# MAKKI_ISMAIL_ESPS3_CAM.net
KiCad netlist of a schematic drawn in EAGLE
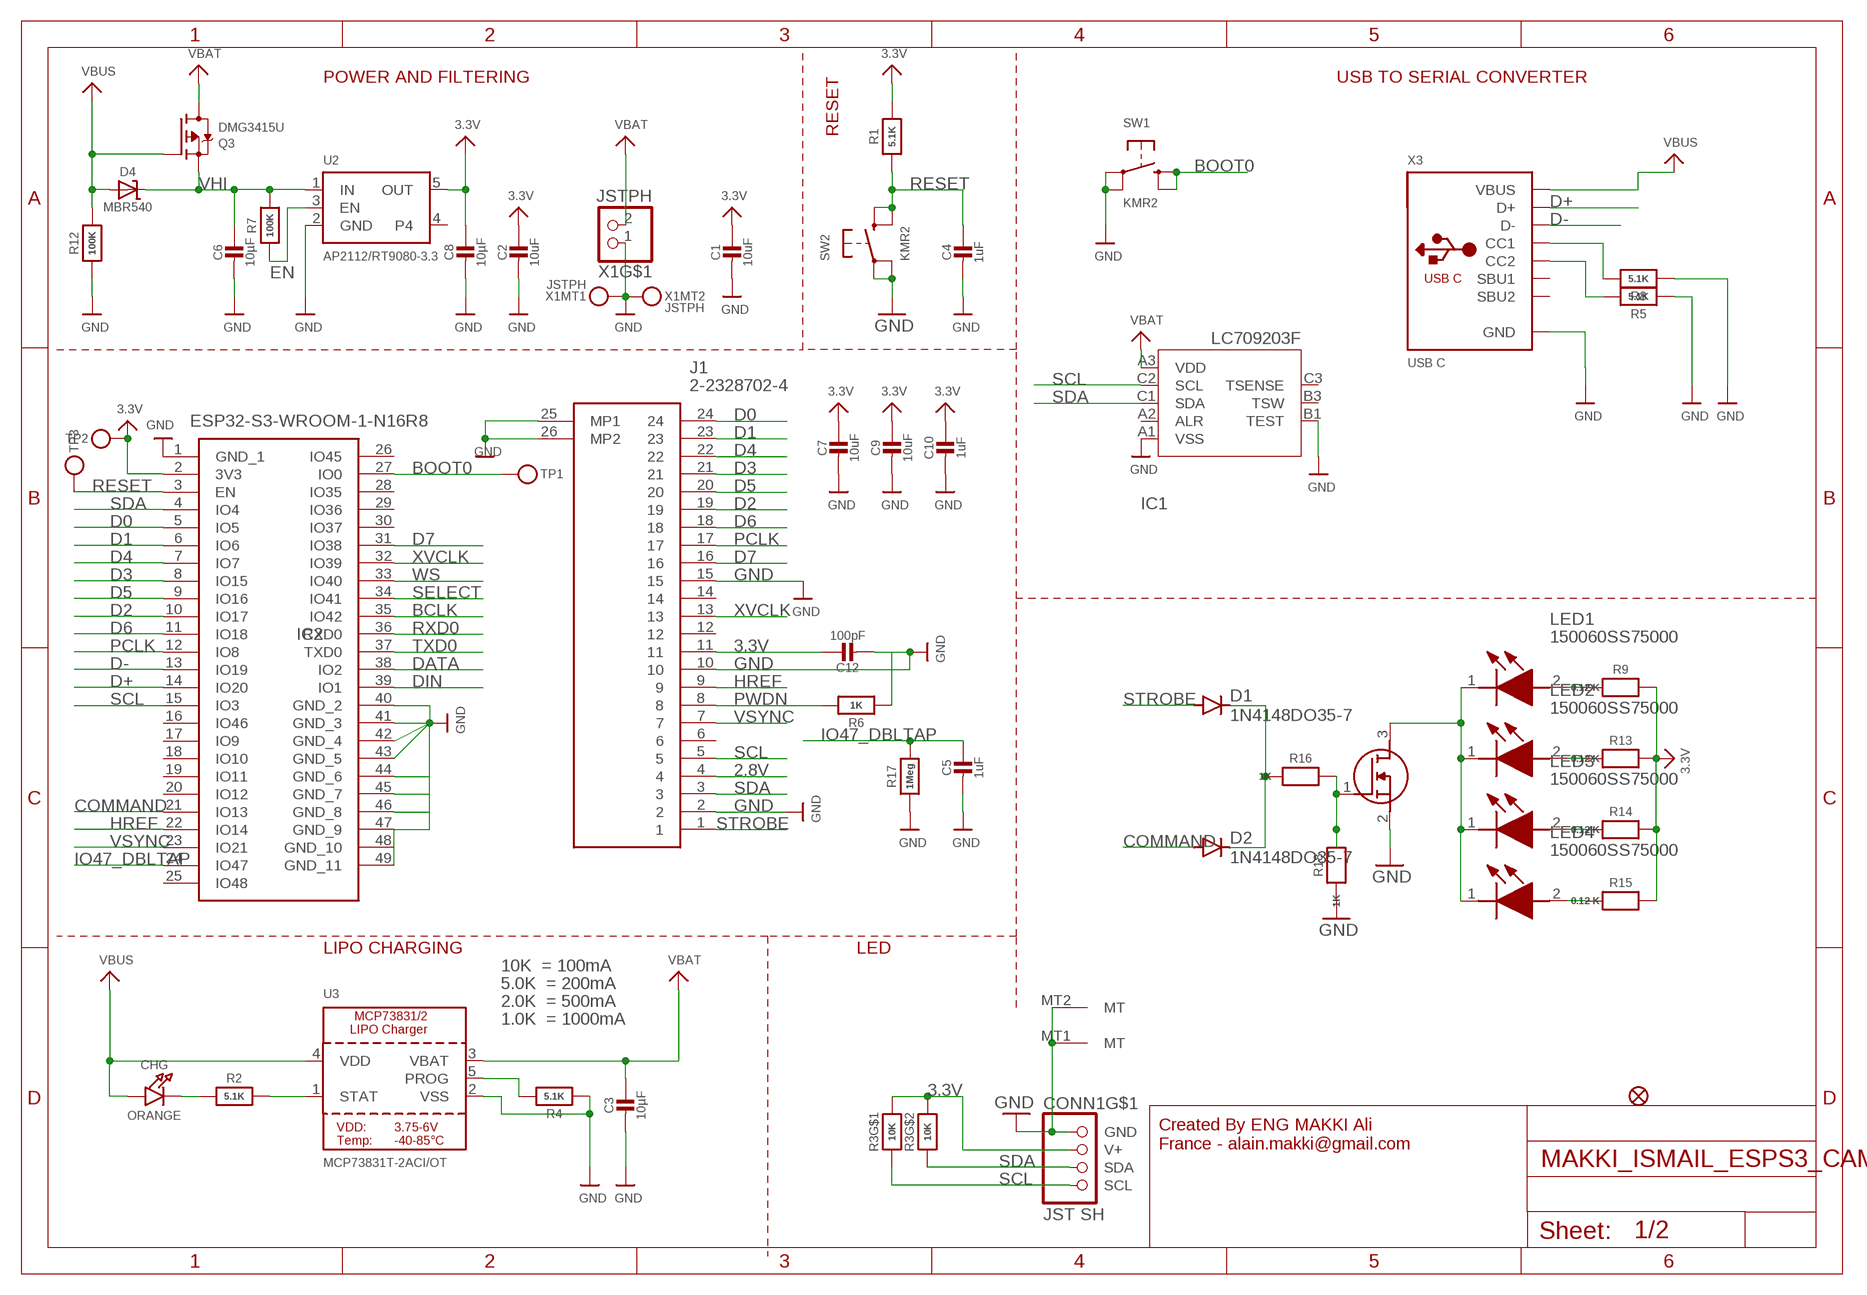
[diagram p0: schematic, sheet 1]
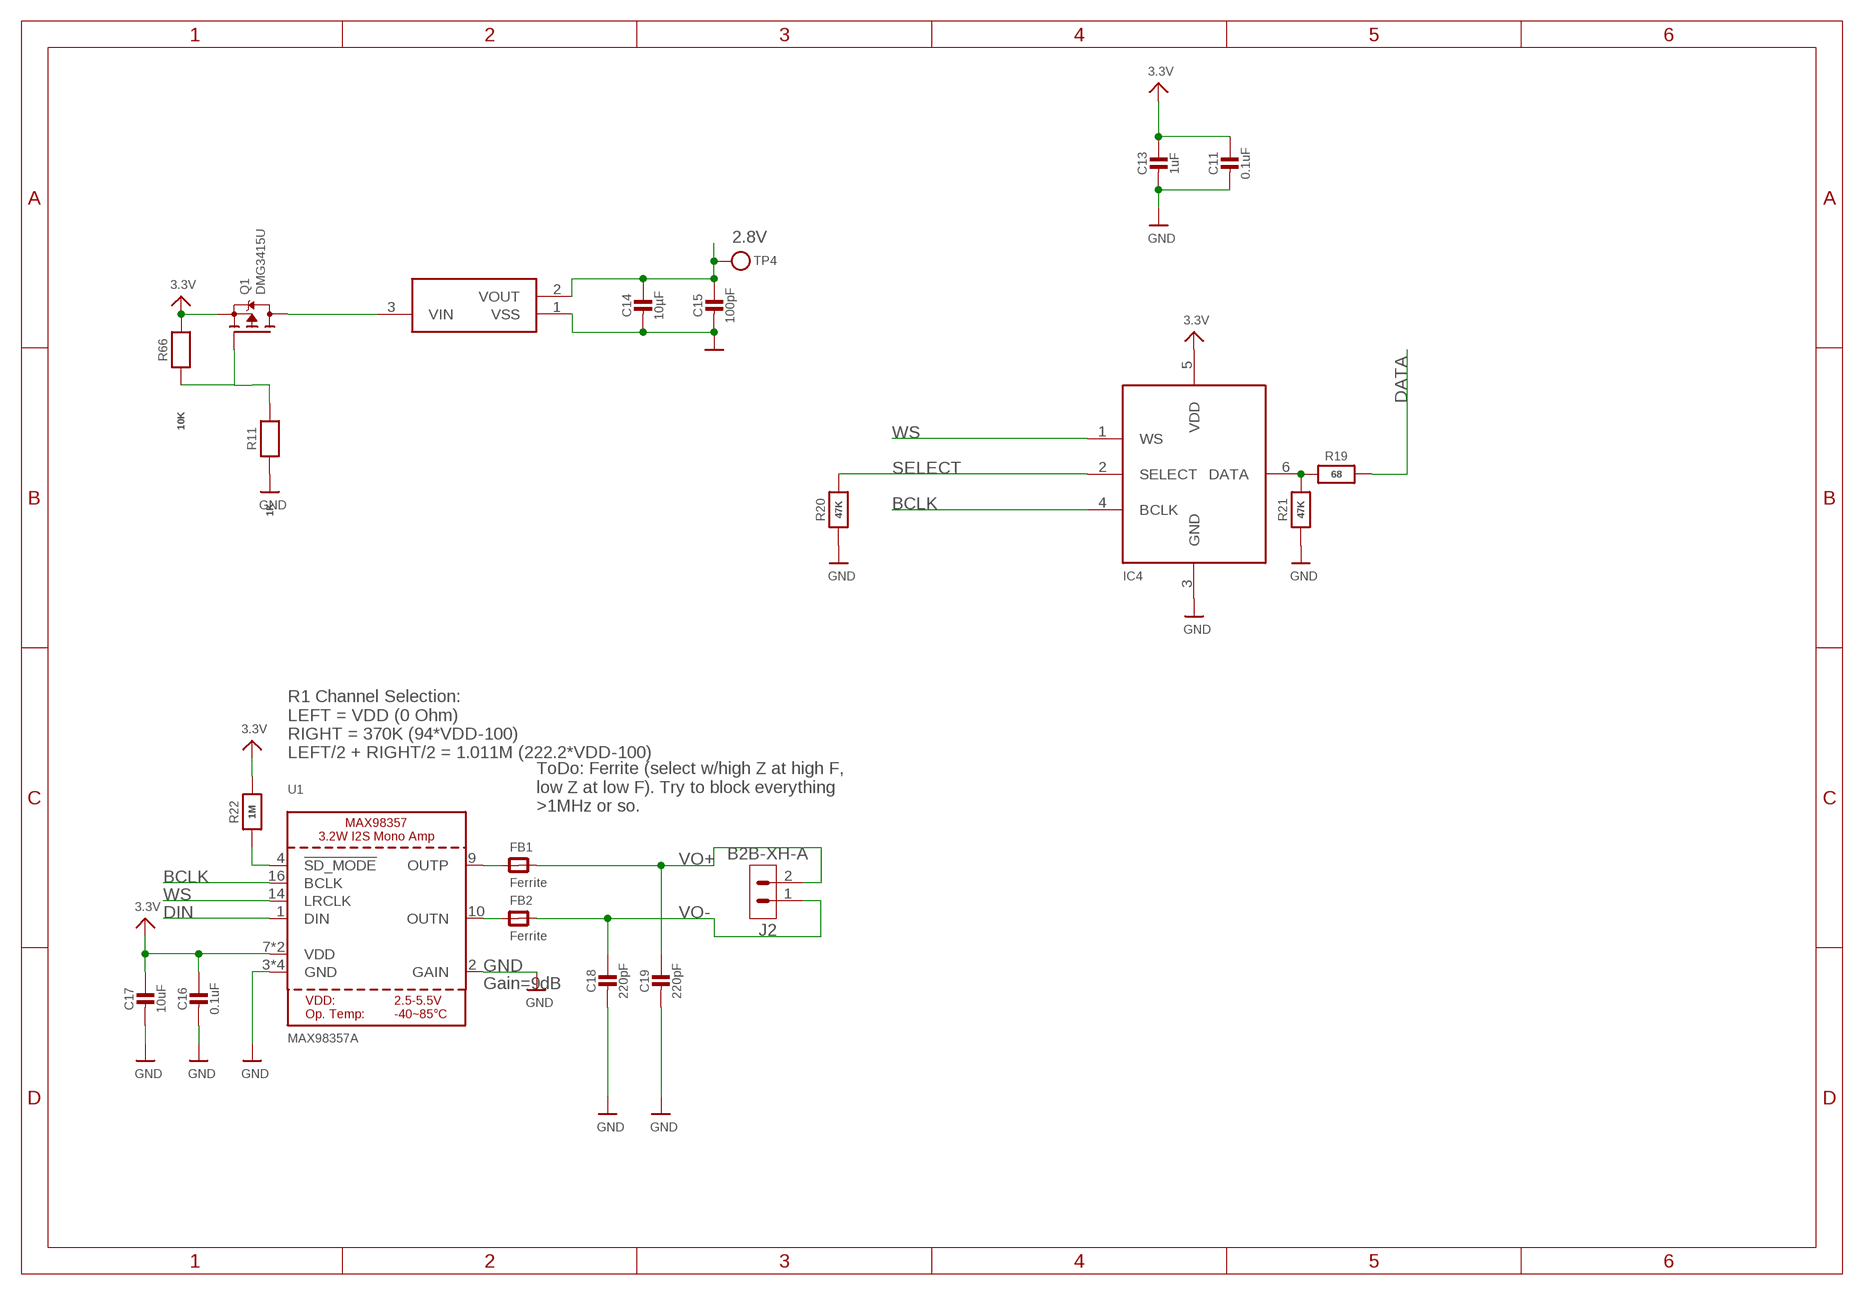
[diagram p1: schematic, sheet 2]

(export (version "E")
  (design (tool "Eeschema 10.0.6"))
  (components
    (comp (ref "C1")
      (value "10uF")
      (footprint "eagle-import:0805-NO")
      (libsource (lib "eagle-import") (part "CAP_CERAMIC0805-NOOUTLINE"))
    )
    (comp (ref "C2")
      (value "10uF")
      (footprint "eagle-import:0805-NO")
      (libsource (lib "eagle-import") (part "CAP_CERAMIC0805-NOOUTLINE"))
    )
    (comp (ref "C3")
      (value "10µF")
      (footprint "eagle-import:0805-NO")
      (libsource (lib "eagle-import") (part "CAP_CERAMIC0805-NOOUTLINE"))
    )
    (comp (ref "C4")
      (value "1uF")
      (footprint "eagle-import:0603-NO")
      (libsource (lib "eagle-import") (part "CAP_CERAMIC0603_NO"))
    )
    (comp (ref "C5")
      (value "1uF")
      (footprint "eagle-import:0603-NO")
      (libsource (lib "eagle-import") (part "CAP_CERAMIC0603_NO"))
    )
    (comp (ref "C6")
      (value "10µF")
      (footprint "eagle-import:0805-NO")
      (libsource (lib "eagle-import") (part "CAP_CERAMIC0805-NOOUTLINE"))
    )
    (comp (ref "C7")
      (value "10uF")
      (footprint "eagle-import:0805-NO")
      (libsource (lib "eagle-import") (part "CAP_CERAMIC0805-NOOUTLINE"))
    )
    (comp (ref "C8")
      (value "10µF")
      (footprint "eagle-import:0805-NO")
      (fields (field (name "REV") "C"))
      (libsource (lib "eagle-import") (part "CAP_CERAMIC0805-NOOUTLINE"))
    )
    (comp (ref "C9")
      (value "10uF")
      (footprint "eagle-import:0805-NO")
      (libsource (lib "eagle-import") (part "CAP_CERAMIC0805-NOOUTLINE"))
    )
    (comp (ref "C10")
      (value "1uF")
      (footprint "eagle-import:0603-NO")
      (libsource (lib "eagle-import") (part "CAP_CERAMIC0603_NO"))
    )
    (comp (ref "C12")
      (value "100pF")
      (footprint "eagle-import:0805-NO")
      (libsource (lib "eagle-import") (part "CAP_CERAMIC0805-NOOUTLINE"))
    )
    (comp (ref "CHG")
      (value "ORANGE")
      (footprint "eagle-import:CHIPLED_0603_NOOUTLINE")
      (libsource (lib "eagle-import") (part "LED0603_NOOUTLINE"))
    )
    (comp (ref "CONN1")
      (value "JST SH")
      (footprint "eagle-import:JST_SH4_RA")
      (libsource (lib "eagle-import") (part "STEMMA_I2C_QTRA"))
    )
    (comp (ref "D1")
      (value "1N4148DO35-7")
      (footprint "eagle-import:DO35-7")
      (libsource (lib "eagle-import") (part "1N4148DO35-7"))
    )
    (comp (ref "D2")
      (value "1N4148DO35-7")
      (footprint "eagle-import:DO35-7")
      (libsource (lib "eagle-import") (part "1N4148DO35-7"))
    )
    (comp (ref "D4")
      (value "MBR540")
      (footprint "eagle-import:SOD-123")
      (libsource (lib "eagle-import") (part "DIODE-SCHOTTKYSOD-123"))
    )
    (comp (ref "IC1")
      (value "LC709203F/MH")
      (footprint "eagle-import:WLCSP9")
      (libsource (lib "eagle-import") (part "LC709203F/MH"))
    )
    (comp (ref "IC2")
      (value "ESP32-S3-WROOM-1-N16R8")
      (footprint "eagle-import:ESP32S3WROOM1N16R8")
      (fields (field (name "MOUSER_PART_NUMBER") "356-ESP32S3WRM1N16R8"))
      (libsource (lib "eagle-import") (part "ESP32-S3-WROOM-1-N16R8"))
    )
    (comp (ref "J1")
      (value "2-2328702-4")
      (footprint "eagle-import:223287024")
      (fields (field (name "MOUSER_PART_NUMBER") "571-2-2328702-4"))
      (libsource (lib "eagle-import") (part "2-2328702-4"))
    )
    (comp (ref "LED1")
      (value "150060SS75000")
      (footprint "eagle-import:LEDC1608X80N")
      (fields (field (name "MOUSER_PART_NUMBER") "710-150060SS75000"))
      (libsource (lib "eagle-import") (part "150060SS75000"))
    )
    (comp (ref "LED2")
      (value "150060SS75000")
      (footprint "eagle-import:LEDC1608X80N")
      (fields (field (name "MOUSER_PART_NUMBER") "710-150060SS75000"))
      (libsource (lib "eagle-import") (part "150060SS75000"))
    )
    (comp (ref "LED3")
      (value "150060SS75000")
      (footprint "eagle-import:LEDC1608X80N")
      (fields (field (name "MOUSER_PART_NUMBER") "710-150060SS75000"))
      (libsource (lib "eagle-import") (part "150060SS75000"))
    )
    (comp (ref "LED4")
      (value "150060SS75000")
      (footprint "eagle-import:LEDC1608X80N")
      (fields (field (name "MOUSER_PART_NUMBER") "710-150060SS75000"))
      (libsource (lib "eagle-import") (part "150060SS75000"))
    )
    (comp (ref "Q2")
      (value "2N7002")
      (footprint "eagle-import:SOT96P240X120-3N")
      (fields (field (name "MOUSER_PART_NUMBER") "512-2N7002"))
      (libsource (lib "eagle-import") (part "2N7002"))
    )
    (comp (ref "Q3")
      (value "DMG3415U")
      (footprint "eagle-import:SOT23-R")
      (libsource (lib "eagle-import") (part "MOSFET-P"))
    )
    (comp (ref "R1")
      (value "5.1K")
      (footprint "eagle-import:0603-NO")
      (libsource (lib "eagle-import") (part "RESISTOR_0603_NOOUT"))
    )
    (comp (ref "R2")
      (value "5.1K")
      (footprint "eagle-import:0603-NO")
      (libsource (lib "eagle-import") (part "RESISTOR_0603_NOOUT"))
    )
    (comp (ref "R3")
      (value "10K")
      (footprint "eagle-import:RESPACK_4X0603")
      (libsource (lib "eagle-import") (part "RESISTOR_4PACK"))
    )
    (comp (ref "R4")
      (value "5.1K")
      (footprint "eagle-import:0603-NO")
      (libsource (lib "eagle-import") (part "RESISTOR_0603_NOOUT"))
    )
    (comp (ref "R5")
      (value "5.1K")
      (footprint "eagle-import:0603-NO")
      (libsource (lib "eagle-import") (part "RESISTOR_0603_NOOUT"))
    )
    (comp (ref "R6")
      (value "1K")
      (footprint "eagle-import:0603-NO")
      (libsource (lib "eagle-import") (part "RESISTOR_0603_NOOUT"))
    )
    (comp (ref "R7")
      (value "100K")
      (footprint "eagle-import:0603-NO")
      (libsource (lib "eagle-import") (part "RESISTOR_0603_NOOUT"))
    )
    (comp (ref "R8")
      (value "5.1K")
      (footprint "eagle-import:0603-NO")
      (libsource (lib "eagle-import") (part "RESISTOR_0603_NOOUT"))
    )
    (comp (ref "R9")
      (value "0.12 K")
      (footprint "eagle-import:0603-NO")
      (libsource (lib "eagle-import") (part "RESISTOR_0603_NOOUT"))
    )
    (comp (ref "R12")
      (value "100K")
      (footprint "eagle-import:0603-NO")
      (libsource (lib "eagle-import") (part "RESISTOR_0603_NOOUT"))
    )
    (comp (ref "R13")
      (value "0.12 K")
      (footprint "eagle-import:0603-NO")
      (libsource (lib "eagle-import") (part "RESISTOR_0603_NOOUT"))
    )
    (comp (ref "R14")
      (value "0.12 K")
      (footprint "eagle-import:0603-NO")
      (libsource (lib "eagle-import") (part "RESISTOR_0603_NOOUT"))
    )
    (comp (ref "R15")
      (value "0.12 K")
      (footprint "eagle-import:0603-NO")
      (libsource (lib "eagle-import") (part "RESISTOR_0603_NOOUT"))
    )
    (comp (ref "R16")
      (value "1K")
      (footprint "eagle-import:0603-NO")
      (libsource (lib "eagle-import") (part "RESISTOR_0603_NOOUT"))
    )
    (comp (ref "R17")
      (value "1Meg")
      (footprint "eagle-import:0603-NO")
      (libsource (lib "eagle-import") (part "RESISTOR_0603_NOOUT"))
    )
    (comp (ref "R18")
      (value "1K")
      (footprint "eagle-import:0603-NO")
      (libsource (lib "eagle-import") (part "RESISTOR_0603_NOOUT"))
    )
    (comp (ref "SW1")
      (value "KMR2")
      (footprint "eagle-import:BTN_KMR2_4.6X2.8")
      (libsource (lib "eagle-import") (part "SWITCH_TACT_SMT4.6X2.8"))
    )
    (comp (ref "SW2")
      (value "KMR2")
      (footprint "eagle-import:BTN_KMR2_4.6X2.8")
      (libsource (lib "eagle-import") (part "SWITCH_TACT_SMT4.6X2.8"))
    )
    (comp (ref "TP1")
      (value "TESTPOINTROUND1.5MMNO")
      (footprint "eagle-import:TESTPOINT_ROUND_1.5MM_NO")
      (libsource (lib "eagle-import") (part "TESTPOINTROUND1.5MMNO"))
    )
    (comp (ref "TP2")
      (value "TESTPOINTROUND1.5MMNO")
      (footprint "eagle-import:TESTPOINT_ROUND_1.5MM_NO")
      (libsource (lib "eagle-import") (part "TESTPOINTROUND1.5MMNO"))
    )
    (comp (ref "TP3")
      (value "TESTPOINTROUND1.5MMNO")
      (footprint "eagle-import:TESTPOINT_ROUND_1.5MM_NO")
      (libsource (lib "eagle-import") (part "TESTPOINTROUND1.5MMNO"))
    )
    (comp (ref "U$34")
      (value "FIDUCIAL_1MM")
      (footprint "eagle-import:FIDUCIAL_1MM")
      (libsource (lib "eagle-import") (part "FIDUCIAL_1MM"))
    )
    (comp (ref "U2")
      (value "AP2112/RT9080-3.3")
      (footprint "eagle-import:SOT23-5")
      (libsource (lib "eagle-import") (part "VREG_SOT23-5"))
    )
    (comp (ref "U3")
      (value "MCP73831T-2ACI/OT")
      (footprint "eagle-import:SOT23-5")
      (libsource (lib "eagle-import") (part "MCP73831/2"))
    )
    (comp (ref "X1")
      (value "JSTPH")
      (footprint "eagle-import:JSTPH2_BATT")
      (libsource (lib "eagle-import") (part "CON_JST_PH_2PIN_MT_BATT"))
    )
    (comp (ref "X3")
      (value "USB C")
      (footprint "eagle-import:USB_C_CUSB31-CFM2AX-01-X")
      (libsource (lib "eagle-import") (part "USB_C"))
    )
    (comp (ref "C11")
      (value "0.1uF")
      (footprint "eagle-import:0603-NO")
      (libsource (lib "eagle-import") (part "CAP_CERAMIC0603_NO"))
    )
    (comp (ref "C13")
      (value "1uF")
      (footprint "eagle-import:0603-NO")
      (libsource (lib "eagle-import") (part "CAP_CERAMIC0603_NO"))
    )
    (comp (ref "C14")
      (value "10µF")
      (footprint "eagle-import:0805-NO")
      (libsource (lib "eagle-import") (part "CAP_CERAMIC0805-NOOUTLINE"))
    )
    (comp (ref "C15")
      (value "100pF")
      (footprint "eagle-import:0805-NO")
      (libsource (lib "eagle-import") (part "CAP_CERAMIC0805-NOOUTLINE"))
    )
    (comp (ref "C16")
      (value "0.1uF")
      (footprint "eagle-import:0805-NO")
      (libsource (lib "eagle-import") (part "CAP_CERAMIC0805-NOOUTLINE"))
    )
    (comp (ref "C17")
      (value "10uF")
      (footprint "eagle-import:0805-NO")
      (libsource (lib "eagle-import") (part "CAP_CERAMIC0805-NOOUTLINE"))
    )
    (comp (ref "C18")
      (value "220pF")
      (footprint "eagle-import:0805-NO")
      (libsource (lib "eagle-import") (part "CAP_CERAMIC0805-NOOUTLINE"))
    )
    (comp (ref "C19")
      (value "220pF")
      (footprint "eagle-import:0805-NO")
      (libsource (lib "eagle-import") (part "CAP_CERAMIC0805-NOOUTLINE"))
    )
    (comp (ref "FB1")
      (value "Ferrite")
      (footprint "eagle-import:0805-NO")
      (libsource (lib "eagle-import") (part "FERRITE-0805NO"))
    )
    (comp (ref "FB2")
      (value "Ferrite")
      (footprint "eagle-import:0805-NO")
      (libsource (lib "eagle-import") (part "FERRITE-0805NO"))
    )
    (comp (ref "IC3")
      (value "XC6206P282MR-G")
      (footprint "eagle-import:SOT95P280X130-3N")
      (fields (field (name "MOUSER_PART_NUMBER") "865-XC6206P282MR-G"))
      (libsource (lib "eagle-import") (part "XC6206P282MR-G"))
    )
    (comp (ref "IC4")
      (value "ICS-43434")
      (footprint "eagle-import:SPH0645LM4H")
      (libsource (lib "eagle-import") (part "MIC_I2S_SPH0645"))
    )
    (comp (ref "J2")
      (value "B2B-XH-A")
      (footprint "eagle-import:B2B-XH-A")
      (fields (field (name "MANUFACTURER") "JST Sales America Inc."))
      (libsource (lib "eagle-import") (part "B2B-XH-A"))
    )
    (comp (ref "Q1")
      (value "DMG3415U")
      (footprint "eagle-import:SOT23-R")
      (libsource (lib "eagle-import") (part "MOSFET-P"))
    )
    (comp (ref "R11")
      (value "1K")
      (footprint "eagle-import:0603-NO")
      (libsource (lib "eagle-import") (part "RESISTOR_0603_NOOUT"))
    )
    (comp (ref "R19")
      (value "68")
      (footprint "eagle-import:0603-NO")
      (libsource (lib "eagle-import") (part "RESISTOR_0603_NOOUT"))
    )
    (comp (ref "R20")
      (value "47K")
      (footprint "eagle-import:0603-NO")
      (libsource (lib "eagle-import") (part "RESISTOR_0603_NOOUT"))
    )
    (comp (ref "R21")
      (value "47K")
      (footprint "eagle-import:0603-NO")
      (libsource (lib "eagle-import") (part "RESISTOR_0603_NOOUT"))
    )
    (comp (ref "R22")
      (value "1M")
      (footprint "eagle-import:0805-NO")
      (libsource (lib "eagle-import") (part "RESISTOR0805_NOOUTLINE"))
    )
    (comp (ref "R66")
      (value "10K")
      (footprint "eagle-import:0603-NO")
      (libsource (lib "eagle-import") (part "RESISTOR_0603_NOOUT"))
    )
    (comp (ref "TP4")
      (value "TESTPOINTROUND1.5MMNO")
      (footprint "eagle-import:TESTPOINT_ROUND_1.5MM_NO")
      (libsource (lib "eagle-import") (part "TESTPOINTROUND1.5MMNO"))
    )
    (comp (ref "U1")
      (value "MAX98357A")
      (footprint "eagle-import:QFN16_3MM")
      (libsource (lib "eagle-import") (part "AUDIOAMP_MAX98357"))
    )
  )
  (nets
    (net (code "1") (name "2.8V") (class "Default")
      (node (ref "C14") (pin "1") (pinfunction "1_1") (pintype "passive"))
      (node (ref "C15") (pin "1") (pinfunction "1_1") (pintype "passive"))
      (node (ref "IC3") (pin "2") (pinfunction "VOUT_2") (pintype "bidirectional"))
      (node (ref "J1") (pin "4") (pinfunction "4_4") (pintype "bidirectional"))
      (node (ref "TP4") (pin "P$1") (pinfunction "P$1_P$1") (pintype "bidirectional"))
    )
    (net (code "2") (name "3.3V") (class "Default")
      (node (ref "C1") (pin "1") (pinfunction "1_1") (pintype "passive"))
      (node (ref "C10") (pin "1") (pinfunction "1_1") (pintype "passive"))
      (node (ref "C11") (pin "1") (pinfunction "1_1") (pintype "passive"))
      (node (ref "C12") (pin "1") (pinfunction "1_1") (pintype "passive"))
      (node (ref "C13") (pin "1") (pinfunction "1_1") (pintype "passive"))
      (node (ref "C16") (pin "1") (pinfunction "1_1") (pintype "passive"))
      (node (ref "C17") (pin "1") (pinfunction "1_1") (pintype "passive"))
      (node (ref "C2") (pin "1") (pinfunction "1_1") (pintype "passive"))
      (node (ref "C7") (pin "1") (pinfunction "1_1") (pintype "passive"))
      (node (ref "C8") (pin "1") (pinfunction "1_1") (pintype "passive"))
      (node (ref "C9") (pin "1") (pinfunction "1_1") (pintype "passive"))
      (node (ref "CONN1") (pin "2") (pinfunction "V+_2") (pintype "passive"))
      (node (ref "IC2") (pin "2") (pinfunction "3V3_2") (pintype "bidirectional"))
      (node (ref "IC4") (pin "5") (pinfunction "VDD_5") (pintype "power_in"))
      (node (ref "J1") (pin "11") (pinfunction "11_11") (pintype "bidirectional"))
      (node (ref "Q1") (pin "2") (pinfunction "S_2") (pintype "passive"))
      (node (ref "R1") (pin "2") (pinfunction "2_2") (pintype "passive"))
      (node (ref "R13") (pin "2") (pinfunction "2_2") (pintype "passive"))
      (node (ref "R14") (pin "2") (pinfunction "2_2") (pintype "passive"))
      (node (ref "R15") (pin "2") (pinfunction "2_2") (pintype "passive"))
      (node (ref "R22") (pin "2") (pinfunction "2_2") (pintype "passive"))
      (node (ref "R3") (pin "7") (pinfunction "2_7") (pintype "passive"))
      (node (ref "R3") (pin "8") (pinfunction "2_8") (pintype "passive"))
      (node (ref "R66") (pin "2") (pinfunction "2_2") (pintype "passive"))
      (node (ref "R9") (pin "2") (pinfunction "2_2") (pintype "passive"))
      (node (ref "TP2") (pin "P$1") (pinfunction "P$1_P$1") (pintype "bidirectional"))
      (node (ref "U1") (pin "7") (pinfunction "VDD_7") (pintype "power_in"))
      (node (ref "U1") (pin "8") (pinfunction "VDD_8") (pintype "power_in"))
      (node (ref "U2") (pin "5") (pinfunction "OUT_5") (pintype "power_in"))
    )
    (net (code "3") (name "BCLK") (class "Default")
      (node (ref "IC2") (pin "35") (pinfunction "IO42_35") (pintype "bidirectional"))
      (node (ref "IC4") (pin "4") (pinfunction "BCLK_4") (pintype "input"))
      (node (ref "U1") (pin "16") (pinfunction "BCLK_16") (pintype "bidirectional"))
    )
    (net (code "4") (name "BOOT0") (class "Default")
      (node (ref "IC2") (pin "27") (pinfunction "IO0_27") (pintype "bidirectional"))
      (node (ref "SW1") (pin "B") (pinfunction "S_B") (pintype "passive"))
      (node (ref "SW1") (pin "B'") (pinfunction "S1_B'") (pintype "passive"))
      (node (ref "TP1") (pin "P$1") (pinfunction "P$1_P$1") (pintype "bidirectional"))
    )
    (net (code "5") (name "COMMAND") (class "Default")
      (node (ref "D2") (pin "A") (pinfunction "A_A") (pintype "passive"))
      (node (ref "IC2") (pin "21") (pinfunction "IO13_21") (pintype "bidirectional"))
    )
    (net (code "6") (name "D+") (class "Default")
      (node (ref "IC2") (pin "14") (pinfunction "IO20_14") (pintype "bidirectional"))
      (node (ref "X3") (pin "A6") (pinfunction "D+_A6") (pintype "bidirectional"))
      (node (ref "X3") (pin "B6") (pinfunction "D+_B6") (pintype "bidirectional"))
    )
    (net (code "7") (name "D-") (class "Default")
      (node (ref "IC2") (pin "13") (pinfunction "IO19_13") (pintype "bidirectional"))
      (node (ref "X3") (pin "A7") (pinfunction "D-_A7") (pintype "bidirectional"))
      (node (ref "X3") (pin "B7") (pinfunction "D-_B7") (pintype "bidirectional"))
    )
    (net (code "8") (name "D0") (class "Default")
      (node (ref "IC2") (pin "5") (pinfunction "IO5_5") (pintype "bidirectional"))
      (node (ref "J1") (pin "24") (pinfunction "24_24") (pintype "bidirectional"))
    )
    (net (code "9") (name "D1") (class "Default")
      (node (ref "IC2") (pin "6") (pinfunction "IO6_6") (pintype "bidirectional"))
      (node (ref "J1") (pin "23") (pinfunction "23_23") (pintype "bidirectional"))
    )
    (net (code "10") (name "D2") (class "Default")
      (node (ref "IC2") (pin "10") (pinfunction "IO17_10") (pintype "bidirectional"))
      (node (ref "J1") (pin "19") (pinfunction "19_19") (pintype "bidirectional"))
    )
    (net (code "11") (name "D3") (class "Default")
      (node (ref "IC2") (pin "8") (pinfunction "IO15_8") (pintype "bidirectional"))
      (node (ref "J1") (pin "21") (pinfunction "21_21") (pintype "bidirectional"))
    )
    (net (code "12") (name "D4") (class "Default")
      (node (ref "IC2") (pin "7") (pinfunction "IO7_7") (pintype "bidirectional"))
      (node (ref "J1") (pin "22") (pinfunction "22_22") (pintype "bidirectional"))
    )
    (net (code "13") (name "D5") (class "Default")
      (node (ref "IC2") (pin "9") (pinfunction "IO16_9") (pintype "bidirectional"))
      (node (ref "J1") (pin "20") (pinfunction "20_20") (pintype "bidirectional"))
    )
    (net (code "14") (name "D6") (class "Default")
      (node (ref "IC2") (pin "11") (pinfunction "IO18_11") (pintype "bidirectional"))
      (node (ref "J1") (pin "18") (pinfunction "18_18") (pintype "bidirectional"))
    )
    (net (code "15") (name "D7") (class "Default")
      (node (ref "IC2") (pin "31") (pinfunction "IO38_31") (pintype "bidirectional"))
      (node (ref "J1") (pin "16") (pinfunction "16_16") (pintype "bidirectional"))
    )
    (net (code "16") (name "DATA") (class "Default")
      (node (ref "IC2") (pin "38") (pinfunction "IO2_38") (pintype "bidirectional"))
      (node (ref "R19") (pin "2") (pinfunction "2_2") (pintype "passive"))
    )
    (net (code "17") (name "DIN") (class "Default")
      (node (ref "IC2") (pin "39") (pinfunction "IO1_39") (pintype "bidirectional"))
      (node (ref "U1") (pin "1") (pinfunction "DIN_1") (pintype "bidirectional"))
    )
    (net (code "18") (name "EN") (class "Default")
      (node (ref "R7") (pin "1") (pinfunction "1_1") (pintype "passive"))
      (node (ref "U2") (pin "3") (pinfunction "EN_3") (pintype "input"))
    )
    (net (code "19") (name "GND") (class "Default")
      (node (ref "C1") (pin "2") (pinfunction "2_2") (pintype "passive"))
      (node (ref "C10") (pin "2") (pinfunction "2_2") (pintype "passive"))
      (node (ref "C11") (pin "2") (pinfunction "2_2") (pintype "passive"))
      (node (ref "C12") (pin "2") (pinfunction "2_2") (pintype "passive"))
      (node (ref "C13") (pin "2") (pinfunction "2_2") (pintype "passive"))
      (node (ref "C14") (pin "2") (pinfunction "2_2") (pintype "passive"))
      (node (ref "C15") (pin "2") (pinfunction "2_2") (pintype "passive"))
      (node (ref "C16") (pin "2") (pinfunction "2_2") (pintype "passive"))
      (node (ref "C17") (pin "2") (pinfunction "2_2") (pintype "passive"))
      (node (ref "C18") (pin "2") (pinfunction "2_2") (pintype "passive"))
      (node (ref "C19") (pin "2") (pinfunction "2_2") (pintype "passive"))
      (node (ref "C2") (pin "2") (pinfunction "2_2") (pintype "passive"))
      (node (ref "C3") (pin "2") (pinfunction "2_2") (pintype "passive"))
      (node (ref "C4") (pin "2") (pinfunction "2_2") (pintype "passive"))
      (node (ref "C5") (pin "2") (pinfunction "2_2") (pintype "passive"))
      (node (ref "C6") (pin "2") (pinfunction "2_2") (pintype "passive"))
      (node (ref "C7") (pin "2") (pinfunction "2_2") (pintype "passive"))
      (node (ref "C8") (pin "2") (pinfunction "2_2") (pintype "passive"))
      (node (ref "C9") (pin "2") (pinfunction "2_2") (pintype "passive"))
      (node (ref "CONN1") (pin "1") (pinfunction "GND_1") (pintype "passive"))
      (node (ref "CONN1") (pin "MT1") (pinfunction "MT_MT1") (pintype "bidirectional"))
      (node (ref "CONN1") (pin "MT2") (pinfunction "MT_MT2") (pintype "bidirectional"))
      (node (ref "IC1") (pin "A1") (pinfunction "VSS_A1") (pintype "power_in"))
      (node (ref "IC1") (pin "B1") (pinfunction "TEST_B1") (pintype "input"))
      (node (ref "IC2") (pin "1") (pinfunction "GND_1_1") (pintype "bidirectional"))
      (node (ref "IC2") (pin "40") (pinfunction "GND_2_40") (pintype "bidirectional"))
      (node (ref "IC2") (pin "41") (pinfunction "GND_3_41") (pintype "bidirectional"))
      (node (ref "IC2") (pin "42") (pinfunction "GND_4_42") (pintype "bidirectional"))
      (node (ref "IC2") (pin "43") (pinfunction "GND_5_43") (pintype "bidirectional"))
      (node (ref "IC2") (pin "44") (pinfunction "GND_6_44") (pintype "bidirectional"))
      (node (ref "IC2") (pin "45") (pinfunction "GND_7_45") (pintype "bidirectional"))
      (node (ref "IC2") (pin "46") (pinfunction "GND_8_46") (pintype "bidirectional"))
      (node (ref "IC2") (pin "47") (pinfunction "GND_9_47") (pintype "bidirectional"))
      (node (ref "IC2") (pin "48") (pinfunction "GND_10_48") (pintype "bidirectional"))
      (node (ref "IC2") (pin "49") (pinfunction "GND_11_49") (pintype "bidirectional"))
      (node (ref "IC3") (pin "1") (pinfunction "VSS_1") (pintype "bidirectional"))
      (node (ref "IC4") (pin "3") (pinfunction "GND_3") (pintype "power_in"))
      (node (ref "J1") (pin "10") (pinfunction "10_10") (pintype "bidirectional"))
      (node (ref "J1") (pin "15") (pinfunction "15_15") (pintype "bidirectional"))
      (node (ref "J1") (pin "2") (pinfunction "2_2") (pintype "bidirectional"))
      (node (ref "J1") (pin "25") (pinfunction "MP1_25") (pintype "bidirectional"))
      (node (ref "J1") (pin "26") (pinfunction "MP2_26") (pintype "bidirectional"))
      (node (ref "Q2") (pin "2") (pinfunction "S_2") (pintype "bidirectional"))
      (node (ref "R11") (pin "1") (pinfunction "1_1") (pintype "passive"))
      (node (ref "R12") (pin "1") (pinfunction "1_1") (pintype "passive"))
      (node (ref "R17") (pin "1") (pinfunction "1_1") (pintype "passive"))
      (node (ref "R18") (pin "1") (pinfunction "1_1") (pintype "passive"))
      (node (ref "R20") (pin "1") (pinfunction "1_1") (pintype "passive"))
      (node (ref "R21") (pin "1") (pinfunction "1_1") (pintype "passive"))
      (node (ref "R4") (pin "1") (pinfunction "1_1") (pintype "passive"))
      (node (ref "R5") (pin "1") (pinfunction "1_1") (pintype "passive"))
      (node (ref "R6") (pin "1") (pinfunction "1_1") (pintype "passive"))
      (node (ref "R8") (pin "1") (pinfunction "1_1") (pintype "passive"))
      (node (ref "SW1") (pin "A") (pinfunction "P_A") (pintype "passive"))
      (node (ref "SW1") (pin "A'") (pinfunction "P1_A'") (pintype "passive"))
      (node (ref "SW2") (pin "A") (pinfunction "P_A") (pintype "passive"))
      (node (ref "SW2") (pin "A'") (pinfunction "P1_A'") (pintype "passive"))
      (node (ref "U1") (pin "11") (pinfunction "GND_11") (pintype "power_in"))
      (node (ref "U1") (pin "15") (pinfunction "GND_15") (pintype "power_in"))
      (node (ref "U1") (pin "2") (pinfunction "GAIN_2") (pintype "bidirectional"))
      (node (ref "U1") (pin "3") (pinfunction "GND_3") (pintype "power_in"))
      (node (ref "U1") (pin "THERMAL") (pinfunction "GND_THERMAL") (pintype "power_in"))
      (node (ref "U2") (pin "2") (pinfunction "GND_2") (pintype "power_in"))
      (node (ref "U3") (pin "2") (pinfunction "VSS_2") (pintype "power_in"))
      (node (ref "X1") (pin "1") (pinfunction "1_1") (pintype "passive"))
      (node (ref "X1") (pin "NC1") (pinfunction "P$1_NC1") (pintype "bidirectional"))
      (node (ref "X1") (pin "NC2") (pinfunction "P$1_NC2") (pintype "bidirectional"))
      (node (ref "X3") (pin "A1B12") (pinfunction "GND_A1B12") (pintype "power_in"))
      (node (ref "X3") (pin "B1A12") (pinfunction "GND_B1A12") (pintype "power_in"))
    )
    (net (code "20") (name "HREF") (class "Default")
      (node (ref "IC2") (pin "22") (pinfunction "IO14_22") (pintype "bidirectional"))
      (node (ref "J1") (pin "9") (pinfunction "9_9") (pintype "bidirectional"))
    )
    (net (code "21") (name "IO47_DBLTAP") (class "Default")
      (node (ref "C5") (pin "1") (pinfunction "1_1") (pintype "passive"))
      (node (ref "IC2") (pin "24") (pinfunction "IO47_24") (pintype "bidirectional"))
      (node (ref "R17") (pin "2") (pinfunction "2_2") (pintype "passive"))
    )
    (net (code "22") (name "Net-(CHG-PadC)") (class "Default")
      (node (ref "CHG") (pin "C") (pinfunction "C_C") (pintype "passive"))
      (node (ref "R2") (pin "1") (pinfunction "1_1") (pintype "passive"))
    )
    (net (code "23") (name "Net-(D1-PadC)") (class "Default")
      (node (ref "D1") (pin "C") (pinfunction "C_C") (pintype "passive"))
      (node (ref "D2") (pin "C") (pinfunction "C_C") (pintype "passive"))
      (node (ref "R16") (pin "1") (pinfunction "1_1") (pintype "passive"))
    )
    (net (code "24") (name "Net-(FB1-P$1)") (class "Default")
      (node (ref "FB1") (pin "1") (pinfunction "P$1_1") (pintype "passive"))
      (node (ref "U1") (pin "9") (pinfunction "OUTP_9") (pintype "output"))
    )
    (net (code "25") (name "Net-(FB2-P$1)") (class "Default")
      (node (ref "FB2") (pin "1") (pinfunction "P$1_1") (pintype "passive"))
      (node (ref "U1") (pin "10") (pinfunction "OUTN_10") (pintype "output"))
    )
    (net (code "26") (name "Net-(IC3-VIN)") (class "Default")
      (node (ref "IC3") (pin "3") (pinfunction "VIN_3") (pintype "bidirectional"))
      (node (ref "Q1") (pin "3") (pinfunction "D_3") (pintype "passive"))
    )
    (net (code "27") (name "Net-(IC4-DATA)") (class "Default")
      (node (ref "IC4") (pin "6") (pinfunction "DATA_6") (pintype "output"))
      (node (ref "R19") (pin "1") (pinfunction "1_1") (pintype "passive"))
      (node (ref "R21") (pin "2") (pinfunction "2_2") (pintype "passive"))
    )
    (net (code "28") (name "Net-(LED1-A)") (class "Default")
      (node (ref "LED1") (pin "2") (pinfunction "A_2") (pintype "bidirectional"))
      (node (ref "R9") (pin "1") (pinfunction "1_1") (pintype "passive"))
    )
    (net (code "29") (name "Net-(LED1-K)") (class "Default")
      (node (ref "LED1") (pin "1") (pinfunction "K_1") (pintype "bidirectional"))
      (node (ref "LED2") (pin "1") (pinfunction "K_1") (pintype "bidirectional"))
      (node (ref "LED3") (pin "1") (pinfunction "K_1") (pintype "bidirectional"))
      (node (ref "LED4") (pin "1") (pinfunction "K_1") (pintype "bidirectional"))
      (node (ref "Q2") (pin "3") (pinfunction "D_3") (pintype "bidirectional"))
    )
    (net (code "30") (name "Net-(LED2-A)") (class "Default")
      (node (ref "LED2") (pin "2") (pinfunction "A_2") (pintype "bidirectional"))
      (node (ref "R13") (pin "1") (pinfunction "1_1") (pintype "passive"))
    )
    (net (code "31") (name "Net-(LED3-A)") (class "Default")
      (node (ref "LED3") (pin "2") (pinfunction "A_2") (pintype "bidirectional"))
      (node (ref "R14") (pin "1") (pinfunction "1_1") (pintype "passive"))
    )
    (net (code "32") (name "Net-(LED4-A)") (class "Default")
      (node (ref "LED4") (pin "2") (pinfunction "A_2") (pintype "bidirectional"))
      (node (ref "R15") (pin "1") (pinfunction "1_1") (pintype "passive"))
    )
    (net (code "33") (name "Net-(Q1-G)") (class "Default")
      (node (ref "Q1") (pin "1") (pinfunction "G_1") (pintype "passive"))
      (node (ref "R11") (pin "2") (pinfunction "2_2") (pintype "passive"))
      (node (ref "R66") (pin "1") (pinfunction "1_1") (pintype "passive"))
    )
    (net (code "34") (name "Net-(Q2-G)") (class "Default")
      (node (ref "Q2") (pin "1") (pinfunction "G_1") (pintype "bidirectional"))
      (node (ref "R16") (pin "2") (pinfunction "2_2") (pintype "passive"))
      (node (ref "R18") (pin "2") (pinfunction "2_2") (pintype "passive"))
    )
    (net (code "35") (name "Net-(U1-~{SD_MODE})") (class "Default")
      (node (ref "R22") (pin "1") (pinfunction "1_1") (pintype "passive"))
      (node (ref "U1") (pin "4") (pinfunction "~{SD_MODE}_4") (pintype "bidirectional"))
    )
    (net (code "36") (name "Net-(U3-PROG)") (class "Default")
      (node (ref "R4") (pin "2") (pinfunction "2_2") (pintype "passive"))
      (node (ref "U3") (pin "5") (pinfunction "PROG_5") (pintype "input"))
    )
    (net (code "37") (name "Net-(U3-STAT)") (class "Default")
      (node (ref "R2") (pin "2") (pinfunction "2_2") (pintype "passive"))
      (node (ref "U3") (pin "1") (pinfunction "STAT_1") (pintype "output"))
    )
    (net (code "38") (name "Net-(X3-CC1)") (class "Default")
      (node (ref "R8") (pin "2") (pinfunction "2_2") (pintype "passive"))
      (node (ref "X3") (pin "A5") (pinfunction "CC1_A5") (pintype "bidirectional"))
    )
    (net (code "39") (name "Net-(X3-CC2)") (class "Default")
      (node (ref "R5") (pin "2") (pinfunction "2_2") (pintype "passive"))
      (node (ref "X3") (pin "B5") (pinfunction "CC2_B5") (pintype "bidirectional"))
    )
    (net (code "40") (name "PCLK") (class "Default")
      (node (ref "IC2") (pin "12") (pinfunction "IO8_12") (pintype "bidirectional"))
      (node (ref "J1") (pin "17") (pinfunction "17_17") (pintype "bidirectional"))
    )
    (net (code "41") (name "PWDN") (class "Default")
      (node (ref "J1") (pin "8") (pinfunction "8_8") (pintype "bidirectional"))
      (node (ref "R6") (pin "2") (pinfunction "2_2") (pintype "passive"))
    )
    (net (code "42") (name "RESET") (class "Default")
      (node (ref "C4") (pin "1") (pinfunction "1_1") (pintype "passive"))
      (node (ref "IC2") (pin "3") (pinfunction "EN_3") (pintype "bidirectional"))
      (node (ref "R1") (pin "1") (pinfunction "1_1") (pintype "passive"))
      (node (ref "SW2") (pin "B") (pinfunction "S_B") (pintype "passive"))
      (node (ref "SW2") (pin "B'") (pinfunction "S1_B'") (pintype "passive"))
      (node (ref "TP3") (pin "P$1") (pinfunction "P$1_P$1") (pintype "bidirectional"))
    )
    (net (code "43") (name "RXD0") (class "Default")
      (node (ref "IC2") (pin "36") (pinfunction "RXD0_36") (pintype "bidirectional"))
    )
    (net (code "44") (name "SCL") (class "Default")
      (node (ref "CONN1") (pin "4") (pinfunction "SCL_4") (pintype "passive"))
      (node (ref "IC1") (pin "C2") (pinfunction "SCL_C2") (pintype "bidirectional"))
      (node (ref "IC2") (pin "15") (pinfunction "IO3_15") (pintype "bidirectional"))
      (node (ref "J1") (pin "5") (pinfunction "5_5") (pintype "bidirectional"))
      (node (ref "R3") (pin "1") (pinfunction "1_1") (pintype "passive"))
    )
    (net (code "45") (name "SDA") (class "Default")
      (node (ref "CONN1") (pin "3") (pinfunction "SDA_3") (pintype "passive"))
      (node (ref "IC1") (pin "C1") (pinfunction "SDA_C1") (pintype "bidirectional"))
      (node (ref "IC2") (pin "4") (pinfunction "IO4_4") (pintype "bidirectional"))
      (node (ref "J1") (pin "3") (pinfunction "3_3") (pintype "bidirectional"))
      (node (ref "R3") (pin "2") (pinfunction "1_2") (pintype "passive"))
    )
    (net (code "46") (name "SELECT") (class "Default")
      (node (ref "IC2") (pin "34") (pinfunction "IO41_34") (pintype "bidirectional"))
      (node (ref "IC4") (pin "2") (pinfunction "SELECT_2") (pintype "input"))
      (node (ref "R20") (pin "2") (pinfunction "2_2") (pintype "passive"))
    )
    (net (code "47") (name "STROBE") (class "Default")
      (node (ref "D1") (pin "A") (pinfunction "A_A") (pintype "passive"))
      (node (ref "J1") (pin "1") (pinfunction "1_1") (pintype "bidirectional"))
    )
    (net (code "48") (name "TXD0") (class "Default")
      (node (ref "IC2") (pin "37") (pinfunction "TXD0_37") (pintype "bidirectional"))
    )
    (net (code "49") (name "VBAT") (class "Default")
      (node (ref "C3") (pin "1") (pinfunction "1_1") (pintype "passive"))
      (node (ref "IC1") (pin "A3") (pinfunction "VDD_A3") (pintype "power_in"))
      (node (ref "Q3") (pin "3") (pinfunction "D_3") (pintype "passive"))
      (node (ref "U3") (pin "3") (pinfunction "VBAT_3") (pintype "power_in"))
      (node (ref "X1") (pin "2") (pinfunction "2_2") (pintype "passive"))
    )
    (net (code "50") (name "VBUS") (class "Default")
      (node (ref "CHG") (pin "A") (pinfunction "A_A") (pintype "passive"))
      (node (ref "D4") (pin "A") (pinfunction "A_A") (pintype "passive"))
      (node (ref "Q3") (pin "1") (pinfunction "G_1") (pintype "passive"))
      (node (ref "R12") (pin "2") (pinfunction "2_2") (pintype "passive"))
      (node (ref "U3") (pin "4") (pinfunction "VDD_4") (pintype "power_in"))
      (node (ref "X3") (pin "A4B9") (pinfunction "VBUS_A4B9") (pintype "power_in"))
      (node (ref "X3") (pin "B4A9") (pinfunction "VBUS_B4A9") (pintype "power_in"))
    )
    (net (code "51") (name "VHI") (class "Default")
      (node (ref "C6") (pin "1") (pinfunction "1_1") (pintype "passive"))
      (node (ref "D4") (pin "C") (pinfunction "C_C") (pintype "passive"))
      (node (ref "Q3") (pin "2") (pinfunction "S_2") (pintype "passive"))
      (node (ref "R7") (pin "2") (pinfunction "2_2") (pintype "passive"))
      (node (ref "U2") (pin "1") (pinfunction "IN_1") (pintype "power_in"))
    )
    (net (code "52") (name "VO+") (class "Default")
      (node (ref "C19") (pin "1") (pinfunction "1_1") (pintype "passive"))
      (node (ref "FB1") (pin "2") (pinfunction "P$2_2") (pintype "passive"))
      (node (ref "J2") (pin "2") (pinfunction "2_2") (pintype "passive"))
    )
    (net (code "53") (name "VO-") (class "Default")
      (node (ref "C18") (pin "1") (pinfunction "1_1") (pintype "passive"))
      (node (ref "FB2") (pin "2") (pinfunction "P$2_2") (pintype "passive"))
      (node (ref "J2") (pin "1") (pinfunction "1_1") (pintype "passive"))
    )
    (net (code "54") (name "VSYNC") (class "Default")
      (node (ref "IC2") (pin "23") (pinfunction "IO21_23") (pintype "bidirectional"))
      (node (ref "J1") (pin "7") (pinfunction "7_7") (pintype "bidirectional"))
    )
    (net (code "55") (name "WS") (class "Default")
      (node (ref "IC2") (pin "33") (pinfunction "IO40_33") (pintype "bidirectional"))
      (node (ref "IC4") (pin "1") (pinfunction "WS_1") (pintype "input"))
      (node (ref "U1") (pin "14") (pinfunction "LRCLK_14") (pintype "bidirectional"))
    )
    (net (code "56") (name "XVCLK") (class "Default")
      (node (ref "IC2") (pin "32") (pinfunction "IO39_32") (pintype "bidirectional"))
      (node (ref "J1") (pin "13") (pinfunction "13_13") (pintype "bidirectional"))
    )
    (net (code "57") (name "unconnected-(IC1-ALR-PadA2)") (class "Default")
      (node (ref "IC1") (pin "A2") (pinfunction "ALR_A2") (pintype "output"))
    )
    (net (code "58") (name "unconnected-(IC1-TSENSE-PadC3)") (class "Default")
      (node (ref "IC1") (pin "C3") (pinfunction "TSENSE_C3") (pintype "passive"))
    )
    (net (code "59") (name "unconnected-(IC1-TSW-PadB3)") (class "Default")
      (node (ref "IC1") (pin "B3") (pinfunction "TSW_B3") (pintype "output"))
    )
    (net (code "60") (name "unconnected-(IC2-IO9-Pad17)") (class "Default")
      (node (ref "IC2") (pin "17") (pinfunction "IO9_17") (pintype "bidirectional"))
    )
    (net (code "61") (name "unconnected-(IC2-IO10-Pad18)") (class "Default")
      (node (ref "IC2") (pin "18") (pinfunction "IO10_18") (pintype "bidirectional"))
    )
    (net (code "62") (name "unconnected-(IC2-IO11-Pad19)") (class "Default")
      (node (ref "IC2") (pin "19") (pinfunction "IO11_19") (pintype "bidirectional"))
    )
    (net (code "63") (name "unconnected-(IC2-IO12-Pad20)") (class "Default")
      (node (ref "IC2") (pin "20") (pinfunction "IO12_20") (pintype "bidirectional"))
    )
    (net (code "64") (name "unconnected-(IC2-IO35-Pad28)") (class "Default")
      (node (ref "IC2") (pin "28") (pinfunction "IO35_28") (pintype "bidirectional"))
    )
    (net (code "65") (name "unconnected-(IC2-IO36-Pad29)") (class "Default")
      (node (ref "IC2") (pin "29") (pinfunction "IO36_29") (pintype "bidirectional"))
    )
    (net (code "66") (name "unconnected-(IC2-IO37-Pad30)") (class "Default")
      (node (ref "IC2") (pin "30") (pinfunction "IO37_30") (pintype "bidirectional"))
    )
    (net (code "67") (name "unconnected-(IC2-IO45-Pad26)") (class "Default")
      (node (ref "IC2") (pin "26") (pinfunction "IO45_26") (pintype "bidirectional"))
    )
    (net (code "68") (name "unconnected-(IC2-IO46-Pad16)") (class "Default")
      (node (ref "IC2") (pin "16") (pinfunction "IO46_16") (pintype "bidirectional"))
    )
    (net (code "69") (name "unconnected-(IC2-IO48-Pad25)") (class "Default")
      (node (ref "IC2") (pin "25") (pinfunction "IO48_25") (pintype "bidirectional"))
    )
    (net (code "70") (name "unconnected-(J1-Pad6)") (class "Default")
      (node (ref "J1") (pin "6") (pinfunction "6_6") (pintype "bidirectional"))
    )
    (net (code "71") (name "unconnected-(J1-Pad12)") (class "Default")
      (node (ref "J1") (pin "12") (pinfunction "12_12") (pintype "bidirectional"))
    )
    (net (code "72") (name "unconnected-(J1-Pad14)") (class "Default")
      (node (ref "J1") (pin "14") (pinfunction "14_14") (pintype "bidirectional"))
    )
    (net (code "73") (name "unconnected-(U2-P4-Pad4)") (class "Default")
      (node (ref "U2") (pin "4") (pinfunction "P4_4") (pintype "bidirectional"))
    )
    (net (code "74") (name "unconnected-(X3-SBU1-PadA8)") (class "Default")
      (node (ref "X3") (pin "A8") (pinfunction "SBU1_A8") (pintype "bidirectional"))
    )
    (net (code "75") (name "unconnected-(X3-SBU2-PadB8)") (class "Default")
      (node (ref "X3") (pin "B8") (pinfunction "SBU2_B8") (pintype "bidirectional"))
    )
  )
)
